# sgtl5000_breakout_board.net
KiCad netlist of a schematic drawn in EAGLE
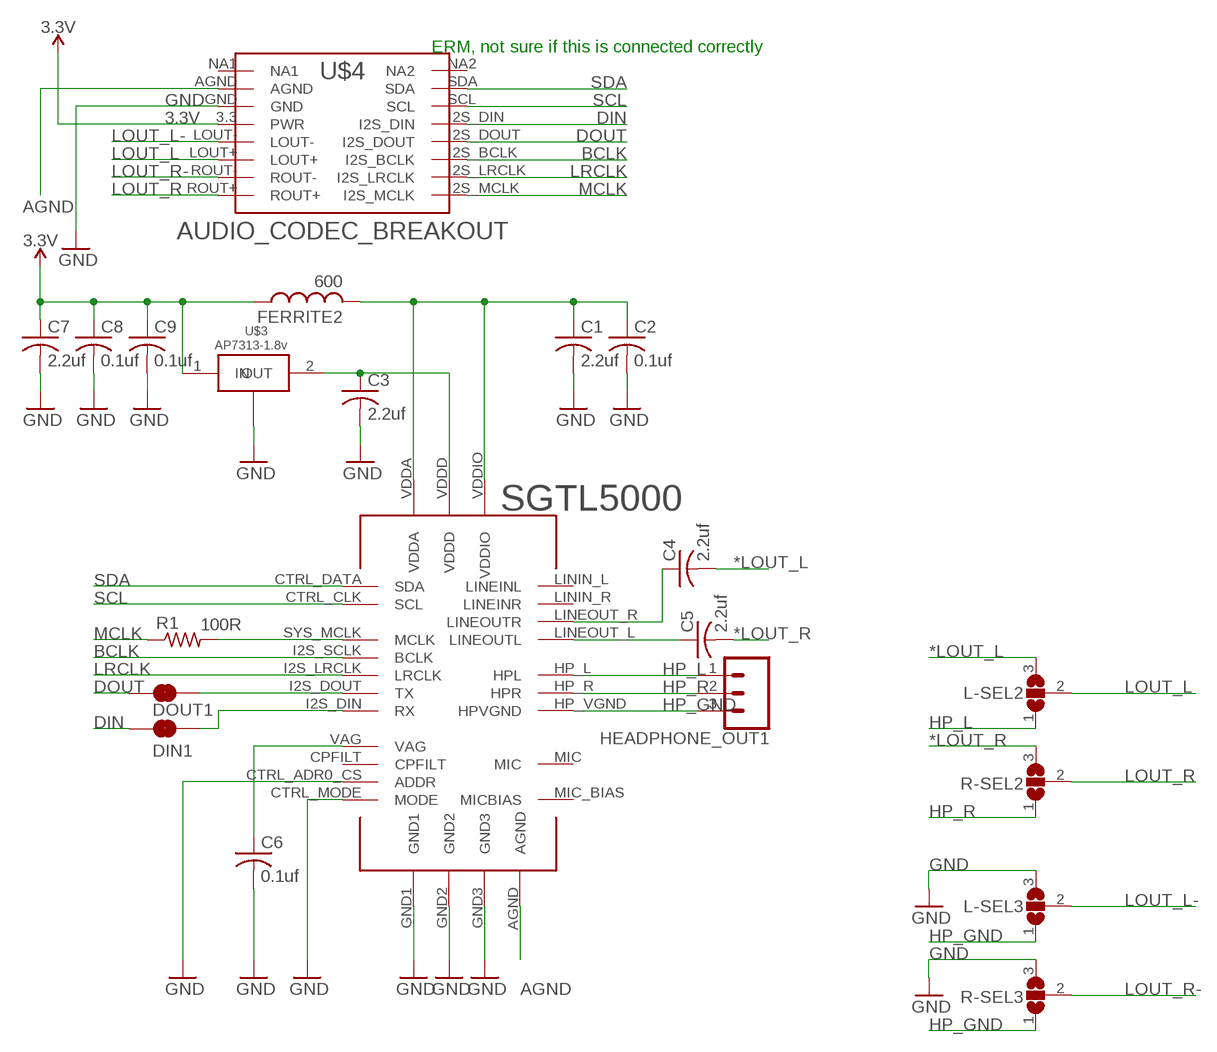
[diagram p0: schematic, sheet 1]

(export (version "E")
  (design (tool "Eeschema 10.0.6"))
  (components
    (comp (ref "C1")
      (value "2.2uf")
      (footprint "eagle-import:C0805")
      (libsource (lib "eagle-import") (part "C-USC0805"))
    )
    (comp (ref "C2")
      (value "0.1uf")
      (footprint "eagle-import:C0805")
      (libsource (lib "eagle-import") (part "C-USC0805"))
    )
    (comp (ref "C3")
      (value "2.2uf")
      (footprint "eagle-import:C0805")
      (libsource (lib "eagle-import") (part "C-USC0805"))
    )
    (comp (ref "C4")
      (value "2.2uf")
      (footprint "eagle-import:C0805")
      (libsource (lib "eagle-import") (part "C-USC0805"))
    )
    (comp (ref "C5")
      (value "2.2uf")
      (footprint "eagle-import:C0805")
      (libsource (lib "eagle-import") (part "C-USC0805"))
    )
    (comp (ref "C6")
      (value "0.1uf")
      (footprint "eagle-import:C0805")
      (libsource (lib "eagle-import") (part "C-USC0805"))
    )
    (comp (ref "C7")
      (value "2.2uf")
      (footprint "eagle-import:C0805")
      (libsource (lib "eagle-import") (part "C-USC0805"))
    )
    (comp (ref "C8")
      (value "0.1uf")
      (footprint "eagle-import:C0805")
      (libsource (lib "eagle-import") (part "C-USC0805"))
    )
    (comp (ref "C9")
      (value "0.1uf")
      (footprint "eagle-import:C0805")
      (libsource (lib "eagle-import") (part "C-USC0805"))
    )
    (comp (ref "DIN1")
      (value "JUMPER-SMT_2_NC_TRACE_SILK")
      (footprint "eagle-import:SMT-JUMPER_2_NC_TRACE_SILK")
      (libsource (lib "eagle-import") (part "JUMPER-SMT_2_NC_TRACE_SILK"))
    )
    (comp (ref "DOUT1")
      (value "JUMPER-SMT_2_NC_TRACE_SILK")
      (footprint "eagle-import:SMT-JUMPER_2_NC_TRACE_SILK")
      (libsource (lib "eagle-import") (part "JUMPER-SMT_2_NC_TRACE_SILK"))
    )
    (comp (ref "FERRITE2")
      (value "600")
      (footprint "eagle-import:RESC0805_N")
      (libsource (lib "eagle-import") (part "INDUCTOR_0805_N"))
    )
    (comp (ref "HEADPHONE_OUT1")
      (value "CONN_03")
      (footprint "eagle-import:1X03")
      (libsource (lib "eagle-import") (part "CONN_03"))
    )
    (comp (ref "L-SEL2")
      (value "SJ2W")
      (footprint "eagle-import:SJ_2")
      (libsource (lib "eagle-import") (part "SJ2W"))
    )
    (comp (ref "L-SEL3")
      (value "SJ2W")
      (footprint "eagle-import:SJ_2")
      (libsource (lib "eagle-import") (part "SJ2W"))
    )
    (comp (ref "R-SEL2")
      (value "SJ2W")
      (footprint "eagle-import:SJ_2")
      (libsource (lib "eagle-import") (part "SJ2W"))
    )
    (comp (ref "R-SEL3")
      (value "SJ2W")
      (footprint "eagle-import:SJ_2")
      (libsource (lib "eagle-import") (part "SJ2W"))
    )
    (comp (ref "R1")
      (value "100R")
      (footprint "eagle-import:M0805")
      (libsource (lib "eagle-import") (part "R-US_M0805"))
    )
    (comp (ref "U$2")
      (value "SGTL5000")
      (footprint "eagle-import:QFN-32-5X5MM")
      (libsource (lib "eagle-import") (part "SGTL5000"))
    )
    (comp (ref "U$3")
      (value "AP7313-1.8v")
      (footprint "eagle-import:SOT-23")
      (libsource (lib "eagle-import") (part "AP7313"))
    )
    (comp (ref "U$4")
      (value "AUDIO_CODEC_BREAKOUT")
      (footprint "eagle-import:HSS_CODEC_BREAKOUT")
      (libsource (lib "eagle-import") (part "AUDIO_CODEC_BREAKOUT"))
    )
  )
  (nets
    (net (code "1") (name "/*LOUT_L") (class "Default")
      (node (ref "C4") (pin "2") (pinfunction "2_2") (pintype "passive"))
      (node (ref "L-SEL2") (pin "3") (pinfunction "3_3") (pintype "passive"))
    )
    (net (code "2") (name "/*LOUT_R") (class "Default")
      (node (ref "C5") (pin "2") (pinfunction "2_2") (pintype "passive"))
      (node (ref "R-SEL2") (pin "3") (pinfunction "3_3") (pintype "passive"))
    )
    (net (code "3") (name "/AGND") (class "Default")
      (node (ref "U$2") (pin "AGND") (pinfunction "AGND_AGND") (pintype "bidirectional"))
      (node (ref "U$4") (pin "AGND") (pinfunction "AGND_AGND") (pintype "bidirectional"))
    )
    (net (code "4") (name "/BCLK") (class "Default")
      (node (ref "U$2") (pin "I2S_SCLK") (pinfunction "BCLK_I2S_SCLK") (pintype "bidirectional"))
      (node (ref "U$4") (pin "I2S_BCLK") (pinfunction "I2S_BCLK_I2S_BCLK") (pintype "bidirectional"))
    )
    (net (code "5") (name "/DIN") (class "Default")
      (node (ref "DIN1") (pin "1") (pinfunction "1_1") (pintype "passive"))
      (node (ref "U$4") (pin "I2S_DIN") (pinfunction "I2S_DIN_I2S_DIN") (pintype "bidirectional"))
    )
    (net (code "6") (name "/DOUT") (class "Default")
      (node (ref "DOUT1") (pin "1") (pinfunction "1_1") (pintype "passive"))
      (node (ref "U$4") (pin "I2S_DOUT") (pinfunction "I2S_DOUT_I2S_DOUT") (pintype "bidirectional"))
    )
    (net (code "7") (name "/HP_GND") (class "Default")
      (node (ref "HEADPHONE_OUT1") (pin "3") (pinfunction "3_3") (pintype "passive"))
      (node (ref "L-SEL3") (pin "1") (pinfunction "1_1") (pintype "passive"))
      (node (ref "R-SEL3") (pin "1") (pinfunction "1_1") (pintype "passive"))
      (node (ref "U$2") (pin "HP_VGND") (pinfunction "HPVGND_HP_VGND") (pintype "bidirectional"))
    )
    (net (code "8") (name "/HP_L") (class "Default")
      (node (ref "HEADPHONE_OUT1") (pin "1") (pinfunction "1_1") (pintype "passive"))
      (node (ref "L-SEL2") (pin "1") (pinfunction "1_1") (pintype "passive"))
      (node (ref "U$2") (pin "HP_L") (pinfunction "HPL_HP_L") (pintype "bidirectional"))
    )
    (net (code "9") (name "/HP_R") (class "Default")
      (node (ref "HEADPHONE_OUT1") (pin "2") (pinfunction "2_2") (pintype "passive"))
      (node (ref "R-SEL2") (pin "1") (pinfunction "1_1") (pintype "passive"))
      (node (ref "U$2") (pin "HP_R") (pinfunction "HPR_HP_R") (pintype "bidirectional"))
    )
    (net (code "10") (name "/LOUT_L") (class "Default")
      (node (ref "L-SEL2") (pin "2") (pinfunction "2_2") (pintype "passive"))
      (node (ref "U$4") (pin "LOUT+") (pinfunction "LOUT+_LOUT+") (pintype "bidirectional"))
    )
    (net (code "11") (name "/LOUT_L-") (class "Default")
      (node (ref "L-SEL3") (pin "2") (pinfunction "2_2") (pintype "passive"))
      (node (ref "U$4") (pin "LOUT-") (pinfunction "LOUT-_LOUT-") (pintype "bidirectional"))
    )
    (net (code "12") (name "/LOUT_R") (class "Default")
      (node (ref "R-SEL2") (pin "2") (pinfunction "2_2") (pintype "passive"))
      (node (ref "U$4") (pin "ROUT+") (pinfunction "ROUT+_ROUT+") (pintype "bidirectional"))
    )
    (net (code "13") (name "/LOUT_R-") (class "Default")
      (node (ref "R-SEL3") (pin "2") (pinfunction "2_2") (pintype "passive"))
      (node (ref "U$4") (pin "ROUT-") (pinfunction "ROUT-_ROUT-") (pintype "bidirectional"))
    )
    (net (code "14") (name "/LRCLK") (class "Default")
      (node (ref "U$2") (pin "I2S_LRCLK") (pinfunction "LRCLK_I2S_LRCLK") (pintype "bidirectional"))
      (node (ref "U$4") (pin "I2S_LRCLK") (pinfunction "I2S_LRCLK_I2S_LRCLK") (pintype "bidirectional"))
    )
    (net (code "15") (name "/MCLK") (class "Default")
      (node (ref "R1") (pin "1") (pinfunction "1_1") (pintype "passive"))
      (node (ref "U$4") (pin "I2S_MCLK") (pinfunction "I2S_MCLK_I2S_MCLK") (pintype "bidirectional"))
    )
    (net (code "16") (name "/SCL") (class "Default")
      (node (ref "U$2") (pin "CTRL_CLK") (pinfunction "SCL_CTRL_CLK") (pintype "bidirectional"))
      (node (ref "U$4") (pin "SCL") (pinfunction "SCL_SCL") (pintype "bidirectional"))
    )
    (net (code "17") (name "/SDA") (class "Default")
      (node (ref "U$2") (pin "CTRL_DATA") (pinfunction "SDA_CTRL_DATA") (pintype "bidirectional"))
      (node (ref "U$4") (pin "SDA") (pinfunction "SDA_SDA") (pintype "bidirectional"))
    )
    (net (code "18") (name "3.3V") (class "Default")
      (node (ref "C7") (pin "1") (pinfunction "1_1") (pintype "passive"))
      (node (ref "C8") (pin "1") (pinfunction "1_1") (pintype "passive"))
      (node (ref "C9") (pin "1") (pinfunction "1_1") (pintype "passive"))
      (node (ref "FERRITE2") (pin "1") (pinfunction "1_1") (pintype "passive"))
      (node (ref "U$3") (pin "1") (pinfunction "IN_1") (pintype "bidirectional"))
      (node (ref "U$4") (pin "3.3") (pinfunction "PWR_3.3") (pintype "bidirectional"))
    )
    (net (code "19") (name "GND") (class "Default")
      (node (ref "C1") (pin "2") (pinfunction "2_2") (pintype "passive"))
      (node (ref "C2") (pin "2") (pinfunction "2_2") (pintype "passive"))
      (node (ref "C3") (pin "2") (pinfunction "2_2") (pintype "passive"))
      (node (ref "C6") (pin "2") (pinfunction "2_2") (pintype "passive"))
      (node (ref "C7") (pin "2") (pinfunction "2_2") (pintype "passive"))
      (node (ref "C8") (pin "2") (pinfunction "2_2") (pintype "passive"))
      (node (ref "C9") (pin "2") (pinfunction "2_2") (pintype "passive"))
      (node (ref "L-SEL3") (pin "3") (pinfunction "3_3") (pintype "passive"))
      (node (ref "R-SEL3") (pin "3") (pinfunction "3_3") (pintype "passive"))
      (node (ref "U$2") (pin "CTRL_ADR0_CS") (pinfunction "ADDR_CTRL_ADR0_CS") (pintype "bidirectional"))
      (node (ref "U$2") (pin "CTRL_MODE") (pinfunction "MODE_CTRL_MODE") (pintype "bidirectional"))
      (node (ref "U$2") (pin "GND1") (pinfunction "GND1_GND1") (pintype "bidirectional"))
      (node (ref "U$2") (pin "GND2") (pinfunction "GND2_GND2") (pintype "bidirectional"))
      (node (ref "U$2") (pin "GND3") (pinfunction "GND3_GND3") (pintype "bidirectional"))
      (node (ref "U$3") (pin "3") (pinfunction "GND_3") (pintype "bidirectional"))
      (node (ref "U$4") (pin "GND") (pinfunction "GND_GND") (pintype "bidirectional"))
    )
    (net (code "20") (name "Net-(C1-Pad1)") (class "Default")
      (node (ref "C1") (pin "1") (pinfunction "1_1") (pintype "passive"))
      (node (ref "C2") (pin "1") (pinfunction "1_1") (pintype "passive"))
      (node (ref "FERRITE2") (pin "2") (pinfunction "2_2") (pintype "passive"))
      (node (ref "U$2") (pin "VDDA") (pinfunction "VDDA_VDDA") (pintype "bidirectional"))
      (node (ref "U$2") (pin "VDDIO") (pinfunction "VDDIO_VDDIO") (pintype "bidirectional"))
    )
    (net (code "21") (name "Net-(C6-Pad1)") (class "Default")
      (node (ref "C6") (pin "1") (pinfunction "1_1") (pintype "passive"))
      (node (ref "U$2") (pin "VAG") (pinfunction "VAG_VAG") (pintype "bidirectional"))
    )
    (net (code "22") (name "Net-(U$2-LINEOUTL)") (class "Default")
      (node (ref "C5") (pin "1") (pinfunction "1_1") (pintype "passive"))
      (node (ref "U$2") (pin "LINEOUT_L") (pinfunction "LINEOUTL_LINEOUT_L") (pintype "bidirectional"))
    )
    (net (code "23") (name "Net-(U$2-LINEOUTR)") (class "Default")
      (node (ref "C4") (pin "1") (pinfunction "1_1") (pintype "passive"))
      (node (ref "U$2") (pin "LINEOUT_R") (pinfunction "LINEOUTR_LINEOUT_R") (pintype "bidirectional"))
    )
    (net (code "24") (name "Net-(U$2-MCLK)") (class "Default")
      (node (ref "R1") (pin "2") (pinfunction "2_2") (pintype "passive"))
      (node (ref "U$2") (pin "SYS_MCLK") (pinfunction "MCLK_SYS_MCLK") (pintype "bidirectional"))
    )
    (net (code "25") (name "Net-(U$2-RX)") (class "Default")
      (node (ref "DIN1") (pin "2") (pinfunction "2_2") (pintype "passive"))
      (node (ref "U$2") (pin "I2S_DIN") (pinfunction "RX_I2S_DIN") (pintype "bidirectional"))
    )
    (net (code "26") (name "Net-(U$2-TX)") (class "Default")
      (node (ref "DOUT1") (pin "2") (pinfunction "2_2") (pintype "passive"))
      (node (ref "U$2") (pin "I2S_DOUT") (pinfunction "TX_I2S_DOUT") (pintype "bidirectional"))
    )
    (net (code "27") (name "Net-(U$3-OUT)") (class "Default")
      (node (ref "C3") (pin "1") (pinfunction "1_1") (pintype "passive"))
      (node (ref "U$2") (pin "VDDD") (pinfunction "VDDD_VDDD") (pintype "bidirectional"))
      (node (ref "U$3") (pin "2") (pinfunction "OUT_2") (pintype "bidirectional"))
    )
    (net (code "28") (name "unconnected-(U$2-LINEINL-PadLININ_L)") (class "Default")
      (node (ref "U$2") (pin "LININ_L") (pinfunction "LINEINL_LININ_L") (pintype "bidirectional"))
    )
    (net (code "29") (name "unconnected-(U$2-LINEINR-PadLININ_R)") (class "Default")
      (node (ref "U$2") (pin "LININ_R") (pinfunction "LINEINR_LININ_R") (pintype "bidirectional"))
    )
    (net (code "30") (name "unconnected-(U$2-MICBIAS-PadMIC_BIAS)") (class "Default")
      (node (ref "U$2") (pin "MIC_BIAS") (pinfunction "MICBIAS_MIC_BIAS") (pintype "bidirectional"))
    )
    (net (code "31") (name "unconnected-(U$2-PadCPFILT)") (class "Default")
      (node (ref "U$2") (pin "CPFILT") (pinfunction "CPFILT_CPFILT") (pintype "bidirectional"))
    )
    (net (code "32") (name "unconnected-(U$2-PadMIC)") (class "Default")
      (node (ref "U$2") (pin "MIC") (pinfunction "MIC_MIC") (pintype "bidirectional"))
    )
    (net (code "33") (name "unconnected-(U$4-PadNA1)") (class "Default")
      (node (ref "U$4") (pin "NA1") (pinfunction "NA1_NA1") (pintype "bidirectional"))
    )
    (net (code "34") (name "unconnected-(U$4-PadNA2)") (class "Default")
      (node (ref "U$4") (pin "NA2") (pinfunction "NA2_NA2") (pintype "bidirectional"))
    )
  )
)
